# Bluetooth.net
KiCad netlist of a schematic drawn in Altium Designer
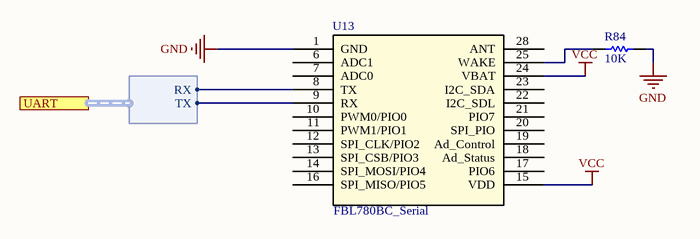
[diagram p0: Bluetooth.SchDoc]

(export (version "E")
  (design (tool "Eeschema 10.0.6"))
  (components
    (comp (ref "R84")
      (value "10K")
      (footprint "R0603[1608]")
      (description "10K 0.25W 1% 0603 (1005 Metric)")
      (fields (field (name "MANUFACTURER") "Vishay / Dale") (field (name "PARTNUMBER") "CRCW060310K0FKEAHP"))
      (libsource (lib "Resistors") (part "RES_10K_0603_1%"))
    )
    (comp (ref "U13")
      (value "FBL780BC_Serial")
      (footprint "FBL780BC_Serial")
      (fields (field (name "MANUFACTURER") "Firmtech"))
      (libsource (lib "General_Component") (part "FBL780BC_Serial"))
    )
  )
  (nets
    (net (code "2") (name "/RX") (class "Default")
      (node (ref "U13") (pin "8") (pinfunction "TX_8") (pintype "passive"))
    )
    (net (code "3") (name "/TX") (class "Default")
      (node (ref "U13") (pin "9") (pinfunction "RX_9") (pintype "passive"))
    )
    (net (code "5") (name "GND") (class "Default")
      (node (ref "R84") (pin "2") (pinfunction "2_2") (pintype "passive"))
      (node (ref "U13") (pin "1") (pinfunction "GND_1") (pintype "power_in"))
    )
    (net (code "6") (name "Net-(U13-WAKE)") (class "Default")
      (node (ref "R84") (pin "1") (pinfunction "1_1") (pintype "passive"))
      (node (ref "U13") (pin "25") (pinfunction "WAKE_25") (pintype "passive"))
    )
    (net (code "7") (name "VCC") (class "Default")
      (node (ref "U13") (pin "15") (pinfunction "VDD_15") (pintype "power_in"))
      (node (ref "U13") (pin "24") (pinfunction "VBAT_24") (pintype "power_in"))
    )
    (net (code "8") (name "unconnected-(U13-ADC0-Pad7)") (class "Default")
      (node (ref "U13") (pin "7") (pinfunction "ADC0_7") (pintype "passive"))
    )
    (net (code "9") (name "unconnected-(U13-ADC1-Pad6)") (class "Default")
      (node (ref "U13") (pin "6") (pinfunction "ADC1_6") (pintype "passive"))
    )
    (net (code "10") (name "unconnected-(U13-ANT-Pad28)") (class "Default")
      (node (ref "U13") (pin "28") (pinfunction "ANT_28") (pintype "passive"))
    )
    (net (code "11") (name "unconnected-(U13-Ad_Control-Pad19)") (class "Default")
      (node (ref "U13") (pin "19") (pinfunction "Ad_Control_19") (pintype "passive"))
    )
    (net (code "12") (name "unconnected-(U13-Ad_Status-Pad18)") (class "Default")
      (node (ref "U13") (pin "18") (pinfunction "Ad_Status_18") (pintype "passive"))
    )
    (net (code "13") (name "unconnected-(U13-I2C_SDA-Pad23)") (class "Default")
      (node (ref "U13") (pin "23") (pinfunction "I2C_SDA_23") (pintype "passive"))
    )
    (net (code "14") (name "unconnected-(U13-I2C_SDL-Pad22)") (class "Default")
      (node (ref "U13") (pin "22") (pinfunction "I2C_SDL_22") (pintype "passive"))
    )
    (net (code "15") (name "unconnected-(U13-PIO6-Pad17)") (class "Default")
      (node (ref "U13") (pin "17") (pinfunction "PIO6_17") (pintype "passive"))
    )
    (net (code "16") (name "unconnected-(U13-PIO7-Pad21)") (class "Default")
      (node (ref "U13") (pin "21") (pinfunction "PIO7_21") (pintype "passive"))
    )
    (net (code "17") (name "unconnected-(U13-PWM0{slash}PIO0-Pad10)") (class "Default")
      (node (ref "U13") (pin "10") (pinfunction "PWM0/PIO0_10") (pintype "passive"))
    )
    (net (code "18") (name "unconnected-(U13-PWM1{slash}PIO1-Pad11)") (class "Default")
      (node (ref "U13") (pin "11") (pinfunction "PWM1/PIO1_11") (pintype "passive"))
    )
    (net (code "19") (name "unconnected-(U13-SPI_CLK{slash}PIO2-Pad12)") (class "Default")
      (node (ref "U13") (pin "12") (pinfunction "SPI_CLK/PIO2_12") (pintype "passive"))
    )
    (net (code "20") (name "unconnected-(U13-SPI_CSB{slash}PIO3-Pad13)") (class "Default")
      (node (ref "U13") (pin "13") (pinfunction "SPI_CSB/PIO3_13") (pintype "passive"))
    )
    (net (code "21") (name "unconnected-(U13-SPI_MISO{slash}PIO5-Pad16)") (class "Default")
      (node (ref "U13") (pin "16") (pinfunction "SPI_MISO/PIO5_16") (pintype "passive"))
    )
    (net (code "22") (name "unconnected-(U13-SPI_MOSI{slash}PIO4-Pad14)") (class "Default")
      (node (ref "U13") (pin "14") (pinfunction "SPI_MOSI/PIO4_14") (pintype "passive"))
    )
    (net (code "23") (name "unconnected-(U13-SPI_PIO-Pad20)") (class "Default")
      (node (ref "U13") (pin "20") (pinfunction "SPI_PIO_20") (pintype "passive"))
    )
  )
)
